# ECUs.net
KiCad netlist of a schematic drawn in Altium Designer
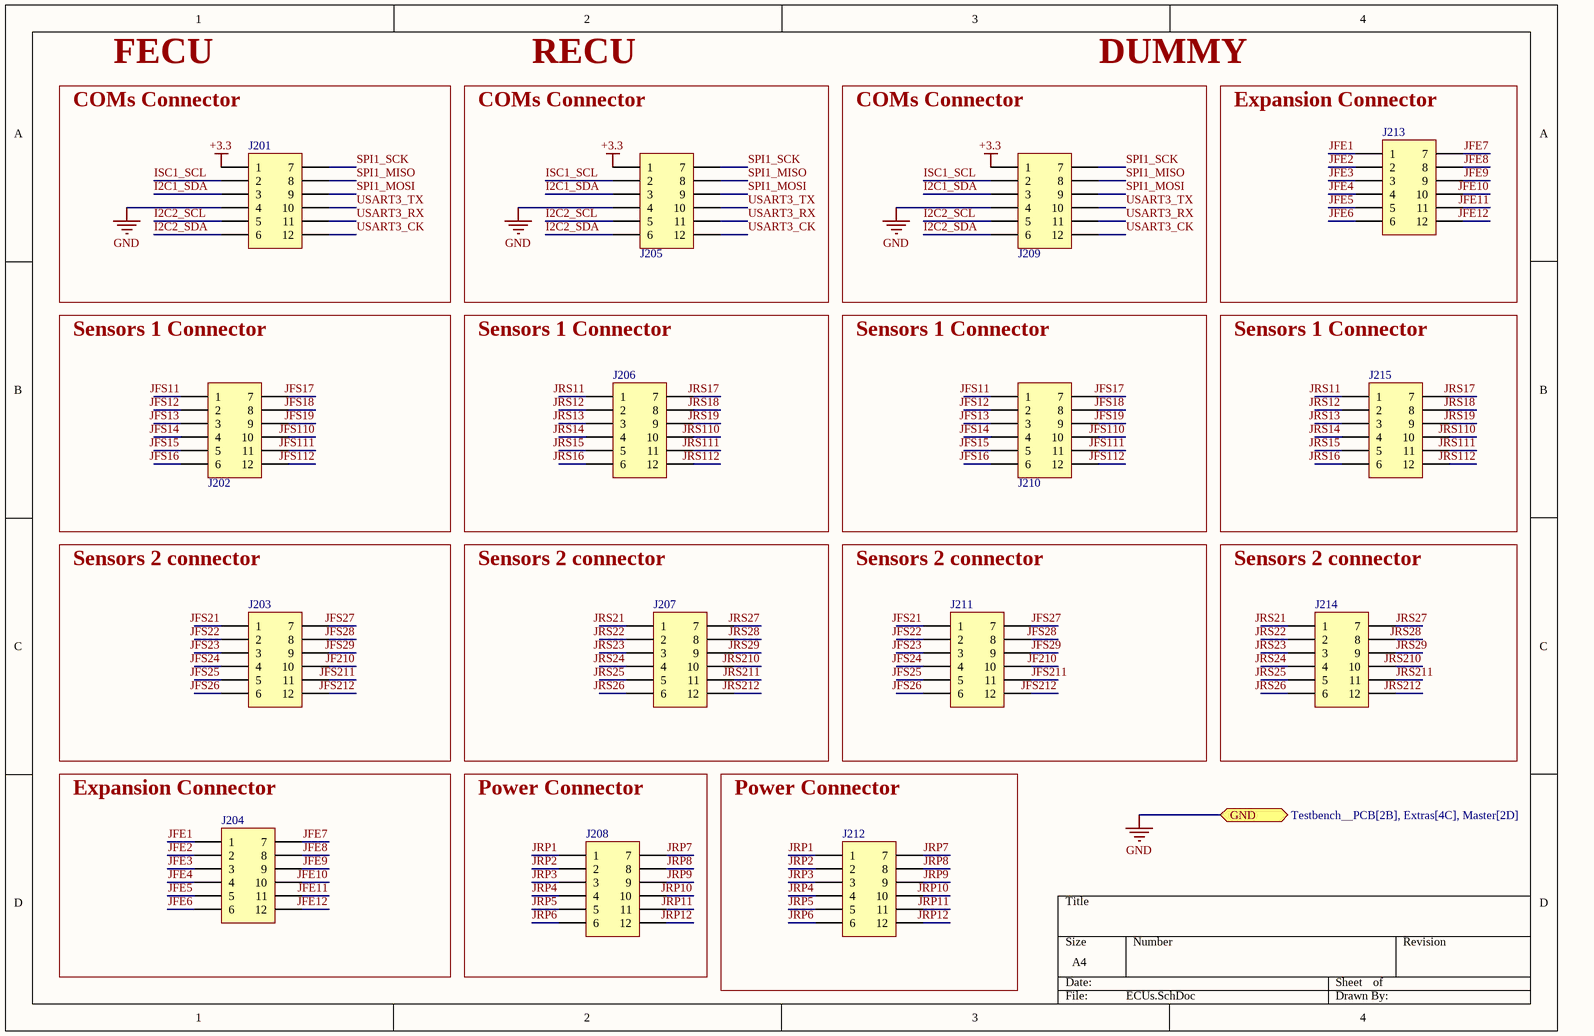
[diagram p0: ECUs.SchDoc]

(export (version "E")
  (design (tool "Eeschema 10.0.6"))
  (components
    (comp (ref "J201")
      (value "1053101112")
      (footprint "J_NanoFit_2x6_V")
      (libsource (lib "Electromechanical") (part "J_NanoFit_2x6_V"))
    )
    (comp (ref "J202")
      (value "1053101112")
      (footprint "J_NanoFit_2x6_V")
      (libsource (lib "Electromechanical") (part "J_NanoFit_2x6_V"))
    )
    (comp (ref "J203")
      (value "1053101112")
      (footprint "J_NanoFit_2x6_V")
      (libsource (lib "Electromechanical") (part "J_NanoFit_2x6_V"))
    )
    (comp (ref "J204")
      (value "1053101112")
      (footprint "J_NanoFit_2x6_V")
      (libsource (lib "Electromechanical") (part "J_NanoFit_2x6_V"))
    )
    (comp (ref "J205")
      (value "1053101112")
      (footprint "J_NanoFit_2x6_V")
      (libsource (lib "Electromechanical") (part "J_NanoFit_2x6_V"))
    )
    (comp (ref "J206")
      (value "1053101112")
      (footprint "J_NanoFit_2x6_V")
      (libsource (lib "Electromechanical") (part "J_NanoFit_2x6_V"))
    )
    (comp (ref "J207")
      (value "1053101112")
      (footprint "J_NanoFit_2x6_V")
      (libsource (lib "Electromechanical") (part "J_NanoFit_2x6_V"))
    )
    (comp (ref "J208")
      (value "1053101112")
      (footprint "J_NanoFit_2x6_V")
      (libsource (lib "Electromechanical") (part "J_NanoFit_2x6_V"))
    )
    (comp (ref "J209")
      (value "1053101112")
      (footprint "J_NanoFit_2x6_V")
      (libsource (lib "Electromechanical") (part "J_NanoFit_2x6_V"))
    )
    (comp (ref "J210")
      (value "1053101112")
      (footprint "J_NanoFit_2x6_V")
      (libsource (lib "Electromechanical") (part "J_NanoFit_2x6_V"))
    )
    (comp (ref "J211")
      (value "1053101112")
      (footprint "J_NanoFit_2x6_V")
      (libsource (lib "Electromechanical") (part "J_NanoFit_2x6_V"))
    )
    (comp (ref "J212")
      (value "1053101112")
      (footprint "J_NanoFit_2x6_V")
      (libsource (lib "Electromechanical") (part "J_NanoFit_2x6_V"))
    )
    (comp (ref "J213")
      (value "1053101112")
      (footprint "J_NanoFit_2x6_V")
      (libsource (lib "Electromechanical") (part "J_NanoFit_2x6_V"))
    )
    (comp (ref "J214")
      (value "1053101112")
      (footprint "J_NanoFit_2x6_V")
      (libsource (lib "Electromechanical") (part "J_NanoFit_2x6_V"))
    )
    (comp (ref "J215")
      (value "1053101112")
      (footprint "J_NanoFit_2x6_V")
      (libsource (lib "Electromechanical") (part "J_NanoFit_2x6_V"))
    )
  )
  (nets
    (net (code "1") (name "+3.3") (class "Default")
      (node (ref "J201") (pin "1") (pinfunction "1_1") (pintype "passive"))
      (node (ref "J205") (pin "1") (pinfunction "1_1") (pintype "passive"))
      (node (ref "J209") (pin "1") (pinfunction "1_1") (pintype "passive"))
    )
    (net (code "2") (name "/I2C1_SDA") (class "Default")
      (node (ref "J201") (pin "3") (pinfunction "3_3") (pintype "passive"))
      (node (ref "J205") (pin "3") (pinfunction "3_3") (pintype "passive"))
      (node (ref "J209") (pin "3") (pinfunction "3_3") (pintype "passive"))
    )
    (net (code "3") (name "/I2C2_SCL") (class "Default")
      (node (ref "J201") (pin "5") (pinfunction "5_5") (pintype "passive"))
      (node (ref "J205") (pin "5") (pinfunction "5_5") (pintype "passive"))
      (node (ref "J209") (pin "5") (pinfunction "5_5") (pintype "passive"))
    )
    (net (code "4") (name "/I2C2_SDA") (class "Default")
      (node (ref "J201") (pin "6") (pinfunction "6_6") (pintype "passive"))
      (node (ref "J205") (pin "6") (pinfunction "6_6") (pintype "passive"))
      (node (ref "J209") (pin "6") (pinfunction "6_6") (pintype "passive"))
    )
    (net (code "5") (name "/ISC1_SCL") (class "Default")
      (node (ref "J201") (pin "2") (pinfunction "2_2") (pintype "passive"))
      (node (ref "J205") (pin "2") (pinfunction "2_2") (pintype "passive"))
      (node (ref "J209") (pin "2") (pinfunction "2_2") (pintype "passive"))
    )
    (net (code "6") (name "/JF210") (class "Default")
      (node (ref "J203") (pin "10") (pinfunction "10_10") (pintype "passive"))
      (node (ref "J211") (pin "10") (pinfunction "10_10") (pintype "passive"))
    )
    (net (code "7") (name "/JFE1") (class "Default")
      (node (ref "J204") (pin "1") (pinfunction "1_1") (pintype "passive"))
      (node (ref "J213") (pin "1") (pinfunction "1_1") (pintype "passive"))
    )
    (net (code "8") (name "/JFE2") (class "Default")
      (node (ref "J204") (pin "2") (pinfunction "2_2") (pintype "passive"))
      (node (ref "J213") (pin "2") (pinfunction "2_2") (pintype "passive"))
    )
    (net (code "9") (name "/JFE3") (class "Default")
      (node (ref "J204") (pin "3") (pinfunction "3_3") (pintype "passive"))
      (node (ref "J213") (pin "3") (pinfunction "3_3") (pintype "passive"))
    )
    (net (code "10") (name "/JFE4") (class "Default")
      (node (ref "J204") (pin "4") (pinfunction "4_4") (pintype "passive"))
      (node (ref "J213") (pin "4") (pinfunction "4_4") (pintype "passive"))
    )
    (net (code "11") (name "/JFE5") (class "Default")
      (node (ref "J204") (pin "5") (pinfunction "5_5") (pintype "passive"))
      (node (ref "J213") (pin "5") (pinfunction "5_5") (pintype "passive"))
    )
    (net (code "12") (name "/JFE6") (class "Default")
      (node (ref "J204") (pin "6") (pinfunction "6_6") (pintype "passive"))
      (node (ref "J213") (pin "6") (pinfunction "6_6") (pintype "passive"))
    )
    (net (code "13") (name "/JFE7") (class "Default")
      (node (ref "J204") (pin "7") (pinfunction "7_7") (pintype "passive"))
      (node (ref "J213") (pin "7") (pinfunction "7_7") (pintype "passive"))
    )
    (net (code "14") (name "/JFE8") (class "Default")
      (node (ref "J204") (pin "8") (pinfunction "8_8") (pintype "passive"))
      (node (ref "J213") (pin "8") (pinfunction "8_8") (pintype "passive"))
    )
    (net (code "15") (name "/JFE9") (class "Default")
      (node (ref "J204") (pin "9") (pinfunction "9_9") (pintype "passive"))
      (node (ref "J213") (pin "9") (pinfunction "9_9") (pintype "passive"))
    )
    (net (code "16") (name "/JFE10") (class "Default")
      (node (ref "J204") (pin "10") (pinfunction "10_10") (pintype "passive"))
      (node (ref "J213") (pin "10") (pinfunction "10_10") (pintype "passive"))
    )
    (net (code "17") (name "/JFE11") (class "Default")
      (node (ref "J204") (pin "11") (pinfunction "11_11") (pintype "passive"))
      (node (ref "J213") (pin "11") (pinfunction "11_11") (pintype "passive"))
    )
    (net (code "18") (name "/JFE12") (class "Default")
      (node (ref "J204") (pin "12") (pinfunction "12_12") (pintype "passive"))
      (node (ref "J213") (pin "12") (pinfunction "12_12") (pintype "passive"))
    )
    (net (code "19") (name "/JFS11") (class "Default")
      (node (ref "J202") (pin "1") (pinfunction "1_1") (pintype "passive"))
      (node (ref "J210") (pin "1") (pinfunction "1_1") (pintype "passive"))
    )
    (net (code "20") (name "/JFS12") (class "Default")
      (node (ref "J202") (pin "2") (pinfunction "2_2") (pintype "passive"))
      (node (ref "J210") (pin "2") (pinfunction "2_2") (pintype "passive"))
    )
    (net (code "21") (name "/JFS13") (class "Default")
      (node (ref "J202") (pin "3") (pinfunction "3_3") (pintype "passive"))
      (node (ref "J210") (pin "3") (pinfunction "3_3") (pintype "passive"))
    )
    (net (code "22") (name "/JFS14") (class "Default")
      (node (ref "J202") (pin "4") (pinfunction "4_4") (pintype "passive"))
      (node (ref "J210") (pin "4") (pinfunction "4_4") (pintype "passive"))
    )
    (net (code "23") (name "/JFS15") (class "Default")
      (node (ref "J202") (pin "5") (pinfunction "5_5") (pintype "passive"))
      (node (ref "J210") (pin "5") (pinfunction "5_5") (pintype "passive"))
    )
    (net (code "24") (name "/JFS16") (class "Default")
      (node (ref "J202") (pin "6") (pinfunction "6_6") (pintype "passive"))
      (node (ref "J210") (pin "6") (pinfunction "6_6") (pintype "passive"))
    )
    (net (code "25") (name "/JFS17") (class "Default")
      (node (ref "J202") (pin "7") (pinfunction "7_7") (pintype "passive"))
      (node (ref "J210") (pin "7") (pinfunction "7_7") (pintype "passive"))
    )
    (net (code "26") (name "/JFS18") (class "Default")
      (node (ref "J202") (pin "8") (pinfunction "8_8") (pintype "passive"))
      (node (ref "J210") (pin "8") (pinfunction "8_8") (pintype "passive"))
    )
    (net (code "27") (name "/JFS19") (class "Default")
      (node (ref "J202") (pin "9") (pinfunction "9_9") (pintype "passive"))
      (node (ref "J210") (pin "9") (pinfunction "9_9") (pintype "passive"))
    )
    (net (code "28") (name "/JFS21") (class "Default")
      (node (ref "J203") (pin "1") (pinfunction "1_1") (pintype "passive"))
      (node (ref "J211") (pin "1") (pinfunction "1_1") (pintype "passive"))
    )
    (net (code "29") (name "/JFS22") (class "Default")
      (node (ref "J203") (pin "2") (pinfunction "2_2") (pintype "passive"))
      (node (ref "J211") (pin "2") (pinfunction "2_2") (pintype "passive"))
    )
    (net (code "30") (name "/JFS23") (class "Default")
      (node (ref "J203") (pin "3") (pinfunction "3_3") (pintype "passive"))
      (node (ref "J211") (pin "3") (pinfunction "3_3") (pintype "passive"))
    )
    (net (code "31") (name "/JFS24") (class "Default")
      (node (ref "J203") (pin "4") (pinfunction "4_4") (pintype "passive"))
      (node (ref "J211") (pin "4") (pinfunction "4_4") (pintype "passive"))
    )
    (net (code "32") (name "/JFS25") (class "Default")
      (node (ref "J203") (pin "5") (pinfunction "5_5") (pintype "passive"))
      (node (ref "J211") (pin "5") (pinfunction "5_5") (pintype "passive"))
    )
    (net (code "33") (name "/JFS26") (class "Default")
      (node (ref "J203") (pin "6") (pinfunction "6_6") (pintype "passive"))
      (node (ref "J211") (pin "6") (pinfunction "6_6") (pintype "passive"))
    )
    (net (code "34") (name "/JFS27") (class "Default")
      (node (ref "J203") (pin "7") (pinfunction "7_7") (pintype "passive"))
      (node (ref "J211") (pin "7") (pinfunction "7_7") (pintype "passive"))
    )
    (net (code "35") (name "/JFS28") (class "Default")
      (node (ref "J203") (pin "8") (pinfunction "8_8") (pintype "passive"))
      (node (ref "J211") (pin "8") (pinfunction "8_8") (pintype "passive"))
    )
    (net (code "36") (name "/JFS29") (class "Default")
      (node (ref "J203") (pin "9") (pinfunction "9_9") (pintype "passive"))
      (node (ref "J211") (pin "9") (pinfunction "9_9") (pintype "passive"))
    )
    (net (code "37") (name "/JFS110") (class "Default")
      (node (ref "J202") (pin "10") (pinfunction "10_10") (pintype "passive"))
      (node (ref "J210") (pin "10") (pinfunction "10_10") (pintype "passive"))
    )
    (net (code "38") (name "/JFS111") (class "Default")
      (node (ref "J202") (pin "11") (pinfunction "11_11") (pintype "passive"))
      (node (ref "J210") (pin "11") (pinfunction "11_11") (pintype "passive"))
    )
    (net (code "39") (name "/JFS112") (class "Default")
      (node (ref "J202") (pin "12") (pinfunction "12_12") (pintype "passive"))
      (node (ref "J210") (pin "12") (pinfunction "12_12") (pintype "passive"))
    )
    (net (code "40") (name "/JFS211") (class "Default")
      (node (ref "J203") (pin "11") (pinfunction "11_11") (pintype "passive"))
      (node (ref "J211") (pin "11") (pinfunction "11_11") (pintype "passive"))
    )
    (net (code "41") (name "/JFS212") (class "Default")
      (node (ref "J203") (pin "12") (pinfunction "12_12") (pintype "passive"))
      (node (ref "J211") (pin "12") (pinfunction "12_12") (pintype "passive"))
    )
    (net (code "42") (name "/JRP1") (class "Default")
      (node (ref "J208") (pin "1") (pinfunction "1_1") (pintype "passive"))
      (node (ref "J212") (pin "1") (pinfunction "1_1") (pintype "passive"))
    )
    (net (code "43") (name "/JRP2") (class "Default")
      (node (ref "J208") (pin "2") (pinfunction "2_2") (pintype "passive"))
      (node (ref "J212") (pin "2") (pinfunction "2_2") (pintype "passive"))
    )
    (net (code "44") (name "/JRP3") (class "Default")
      (node (ref "J208") (pin "3") (pinfunction "3_3") (pintype "passive"))
      (node (ref "J212") (pin "3") (pinfunction "3_3") (pintype "passive"))
    )
    (net (code "45") (name "/JRP4") (class "Default")
      (node (ref "J208") (pin "4") (pinfunction "4_4") (pintype "passive"))
      (node (ref "J212") (pin "4") (pinfunction "4_4") (pintype "passive"))
    )
    (net (code "46") (name "/JRP5") (class "Default")
      (node (ref "J208") (pin "5") (pinfunction "5_5") (pintype "passive"))
      (node (ref "J212") (pin "5") (pinfunction "5_5") (pintype "passive"))
    )
    (net (code "47") (name "/JRP6") (class "Default")
      (node (ref "J208") (pin "6") (pinfunction "6_6") (pintype "passive"))
      (node (ref "J212") (pin "6") (pinfunction "6_6") (pintype "passive"))
    )
    (net (code "48") (name "/JRP7") (class "Default")
      (node (ref "J208") (pin "7") (pinfunction "7_7") (pintype "passive"))
      (node (ref "J212") (pin "7") (pinfunction "7_7") (pintype "passive"))
    )
    (net (code "49") (name "/JRP8") (class "Default")
      (node (ref "J208") (pin "8") (pinfunction "8_8") (pintype "passive"))
      (node (ref "J212") (pin "8") (pinfunction "8_8") (pintype "passive"))
    )
    (net (code "50") (name "/JRP9") (class "Default")
      (node (ref "J208") (pin "9") (pinfunction "9_9") (pintype "passive"))
      (node (ref "J212") (pin "9") (pinfunction "9_9") (pintype "passive"))
    )
    (net (code "51") (name "/JRP10") (class "Default")
      (node (ref "J208") (pin "10") (pinfunction "10_10") (pintype "passive"))
      (node (ref "J212") (pin "10") (pinfunction "10_10") (pintype "passive"))
    )
    (net (code "52") (name "/JRP11") (class "Default")
      (node (ref "J208") (pin "11") (pinfunction "11_11") (pintype "passive"))
      (node (ref "J212") (pin "11") (pinfunction "11_11") (pintype "passive"))
    )
    (net (code "53") (name "/JRP12") (class "Default")
      (node (ref "J208") (pin "12") (pinfunction "12_12") (pintype "passive"))
      (node (ref "J212") (pin "12") (pinfunction "12_12") (pintype "passive"))
    )
    (net (code "54") (name "/JRS11") (class "Default")
      (node (ref "J206") (pin "1") (pinfunction "1_1") (pintype "passive"))
      (node (ref "J215") (pin "1") (pinfunction "1_1") (pintype "passive"))
    )
    (net (code "55") (name "/JRS12") (class "Default")
      (node (ref "J206") (pin "2") (pinfunction "2_2") (pintype "passive"))
      (node (ref "J215") (pin "2") (pinfunction "2_2") (pintype "passive"))
    )
    (net (code "56") (name "/JRS13") (class "Default")
      (node (ref "J206") (pin "3") (pinfunction "3_3") (pintype "passive"))
      (node (ref "J215") (pin "3") (pinfunction "3_3") (pintype "passive"))
    )
    (net (code "57") (name "/JRS14") (class "Default")
      (node (ref "J206") (pin "4") (pinfunction "4_4") (pintype "passive"))
      (node (ref "J215") (pin "4") (pinfunction "4_4") (pintype "passive"))
    )
    (net (code "58") (name "/JRS15") (class "Default")
      (node (ref "J206") (pin "5") (pinfunction "5_5") (pintype "passive"))
      (node (ref "J215") (pin "5") (pinfunction "5_5") (pintype "passive"))
    )
    (net (code "59") (name "/JRS16") (class "Default")
      (node (ref "J206") (pin "6") (pinfunction "6_6") (pintype "passive"))
      (node (ref "J215") (pin "6") (pinfunction "6_6") (pintype "passive"))
    )
    (net (code "60") (name "/JRS17") (class "Default")
      (node (ref "J206") (pin "7") (pinfunction "7_7") (pintype "passive"))
      (node (ref "J215") (pin "7") (pinfunction "7_7") (pintype "passive"))
    )
    (net (code "61") (name "/JRS18") (class "Default")
      (node (ref "J206") (pin "8") (pinfunction "8_8") (pintype "passive"))
      (node (ref "J215") (pin "8") (pinfunction "8_8") (pintype "passive"))
    )
    (net (code "62") (name "/JRS19") (class "Default")
      (node (ref "J206") (pin "9") (pinfunction "9_9") (pintype "passive"))
      (node (ref "J215") (pin "9") (pinfunction "9_9") (pintype "passive"))
    )
    (net (code "63") (name "/JRS21") (class "Default")
      (node (ref "J207") (pin "1") (pinfunction "1_1") (pintype "passive"))
      (node (ref "J214") (pin "1") (pinfunction "1_1") (pintype "passive"))
    )
    (net (code "64") (name "/JRS22") (class "Default")
      (node (ref "J207") (pin "2") (pinfunction "2_2") (pintype "passive"))
      (node (ref "J214") (pin "2") (pinfunction "2_2") (pintype "passive"))
    )
    (net (code "65") (name "/JRS23") (class "Default")
      (node (ref "J207") (pin "3") (pinfunction "3_3") (pintype "passive"))
      (node (ref "J214") (pin "3") (pinfunction "3_3") (pintype "passive"))
    )
    (net (code "66") (name "/JRS24") (class "Default")
      (node (ref "J207") (pin "4") (pinfunction "4_4") (pintype "passive"))
      (node (ref "J214") (pin "4") (pinfunction "4_4") (pintype "passive"))
    )
    (net (code "67") (name "/JRS25") (class "Default")
      (node (ref "J207") (pin "5") (pinfunction "5_5") (pintype "passive"))
      (node (ref "J214") (pin "5") (pinfunction "5_5") (pintype "passive"))
    )
    (net (code "68") (name "/JRS26") (class "Default")
      (node (ref "J207") (pin "6") (pinfunction "6_6") (pintype "passive"))
      (node (ref "J214") (pin "6") (pinfunction "6_6") (pintype "passive"))
    )
    (net (code "69") (name "/JRS27") (class "Default")
      (node (ref "J207") (pin "7") (pinfunction "7_7") (pintype "passive"))
      (node (ref "J214") (pin "7") (pinfunction "7_7") (pintype "passive"))
    )
    (net (code "70") (name "/JRS28") (class "Default")
      (node (ref "J207") (pin "8") (pinfunction "8_8") (pintype "passive"))
      (node (ref "J214") (pin "8") (pinfunction "8_8") (pintype "passive"))
    )
    (net (code "71") (name "/JRS29") (class "Default")
      (node (ref "J207") (pin "9") (pinfunction "9_9") (pintype "passive"))
      (node (ref "J214") (pin "9") (pinfunction "9_9") (pintype "passive"))
    )
    (net (code "72") (name "/JRS110") (class "Default")
      (node (ref "J206") (pin "10") (pinfunction "10_10") (pintype "passive"))
      (node (ref "J215") (pin "10") (pinfunction "10_10") (pintype "passive"))
    )
    (net (code "73") (name "/JRS111") (class "Default")
      (node (ref "J206") (pin "11") (pinfunction "11_11") (pintype "passive"))
      (node (ref "J215") (pin "11") (pinfunction "11_11") (pintype "passive"))
    )
    (net (code "74") (name "/JRS112") (class "Default")
      (node (ref "J206") (pin "12") (pinfunction "12_12") (pintype "passive"))
      (node (ref "J215") (pin "12") (pinfunction "12_12") (pintype "passive"))
    )
    (net (code "75") (name "/JRS210") (class "Default")
      (node (ref "J207") (pin "10") (pinfunction "10_10") (pintype "passive"))
      (node (ref "J214") (pin "10") (pinfunction "10_10") (pintype "passive"))
    )
    (net (code "76") (name "/JRS211") (class "Default")
      (node (ref "J207") (pin "11") (pinfunction "11_11") (pintype "passive"))
      (node (ref "J214") (pin "11") (pinfunction "11_11") (pintype "passive"))
    )
    (net (code "77") (name "/JRS212") (class "Default")
      (node (ref "J207") (pin "12") (pinfunction "12_12") (pintype "passive"))
      (node (ref "J214") (pin "12") (pinfunction "12_12") (pintype "passive"))
    )
    (net (code "78") (name "/SPI1_MISO") (class "Default")
      (node (ref "J201") (pin "8") (pinfunction "8_8") (pintype "passive"))
      (node (ref "J205") (pin "8") (pinfunction "8_8") (pintype "passive"))
      (node (ref "J209") (pin "8") (pinfunction "8_8") (pintype "passive"))
    )
    (net (code "79") (name "/SPI1_MOSI") (class "Default")
      (node (ref "J201") (pin "9") (pinfunction "9_9") (pintype "passive"))
      (node (ref "J205") (pin "9") (pinfunction "9_9") (pintype "passive"))
      (node (ref "J209") (pin "9") (pinfunction "9_9") (pintype "passive"))
    )
    (net (code "80") (name "/SPI1_SCK") (class "Default")
      (node (ref "J201") (pin "7") (pinfunction "7_7") (pintype "passive"))
      (node (ref "J205") (pin "7") (pinfunction "7_7") (pintype "passive"))
      (node (ref "J209") (pin "7") (pinfunction "7_7") (pintype "passive"))
    )
    (net (code "81") (name "/USART3_CK") (class "Default")
      (node (ref "J201") (pin "12") (pinfunction "12_12") (pintype "passive"))
      (node (ref "J205") (pin "12") (pinfunction "12_12") (pintype "passive"))
      (node (ref "J209") (pin "12") (pinfunction "12_12") (pintype "passive"))
    )
    (net (code "82") (name "/USART3_RX") (class "Default")
      (node (ref "J201") (pin "11") (pinfunction "11_11") (pintype "passive"))
      (node (ref "J205") (pin "11") (pinfunction "11_11") (pintype "passive"))
      (node (ref "J209") (pin "11") (pinfunction "11_11") (pintype "passive"))
    )
    (net (code "83") (name "/USART3_TX") (class "Default")
      (node (ref "J201") (pin "10") (pinfunction "10_10") (pintype "passive"))
      (node (ref "J205") (pin "10") (pinfunction "10_10") (pintype "passive"))
      (node (ref "J209") (pin "10") (pinfunction "10_10") (pintype "passive"))
    )
    (net (code "84") (name "GND") (class "Default")
      (node (ref "J201") (pin "4") (pinfunction "4_4") (pintype "passive"))
      (node (ref "J205") (pin "4") (pinfunction "4_4") (pintype "passive"))
      (node (ref "J209") (pin "4") (pinfunction "4_4") (pintype "passive"))
    )
  )
)
